# SCH_espweather_2025-04-03.net
KiCad netlist of a schematic drawn in EasyEDA
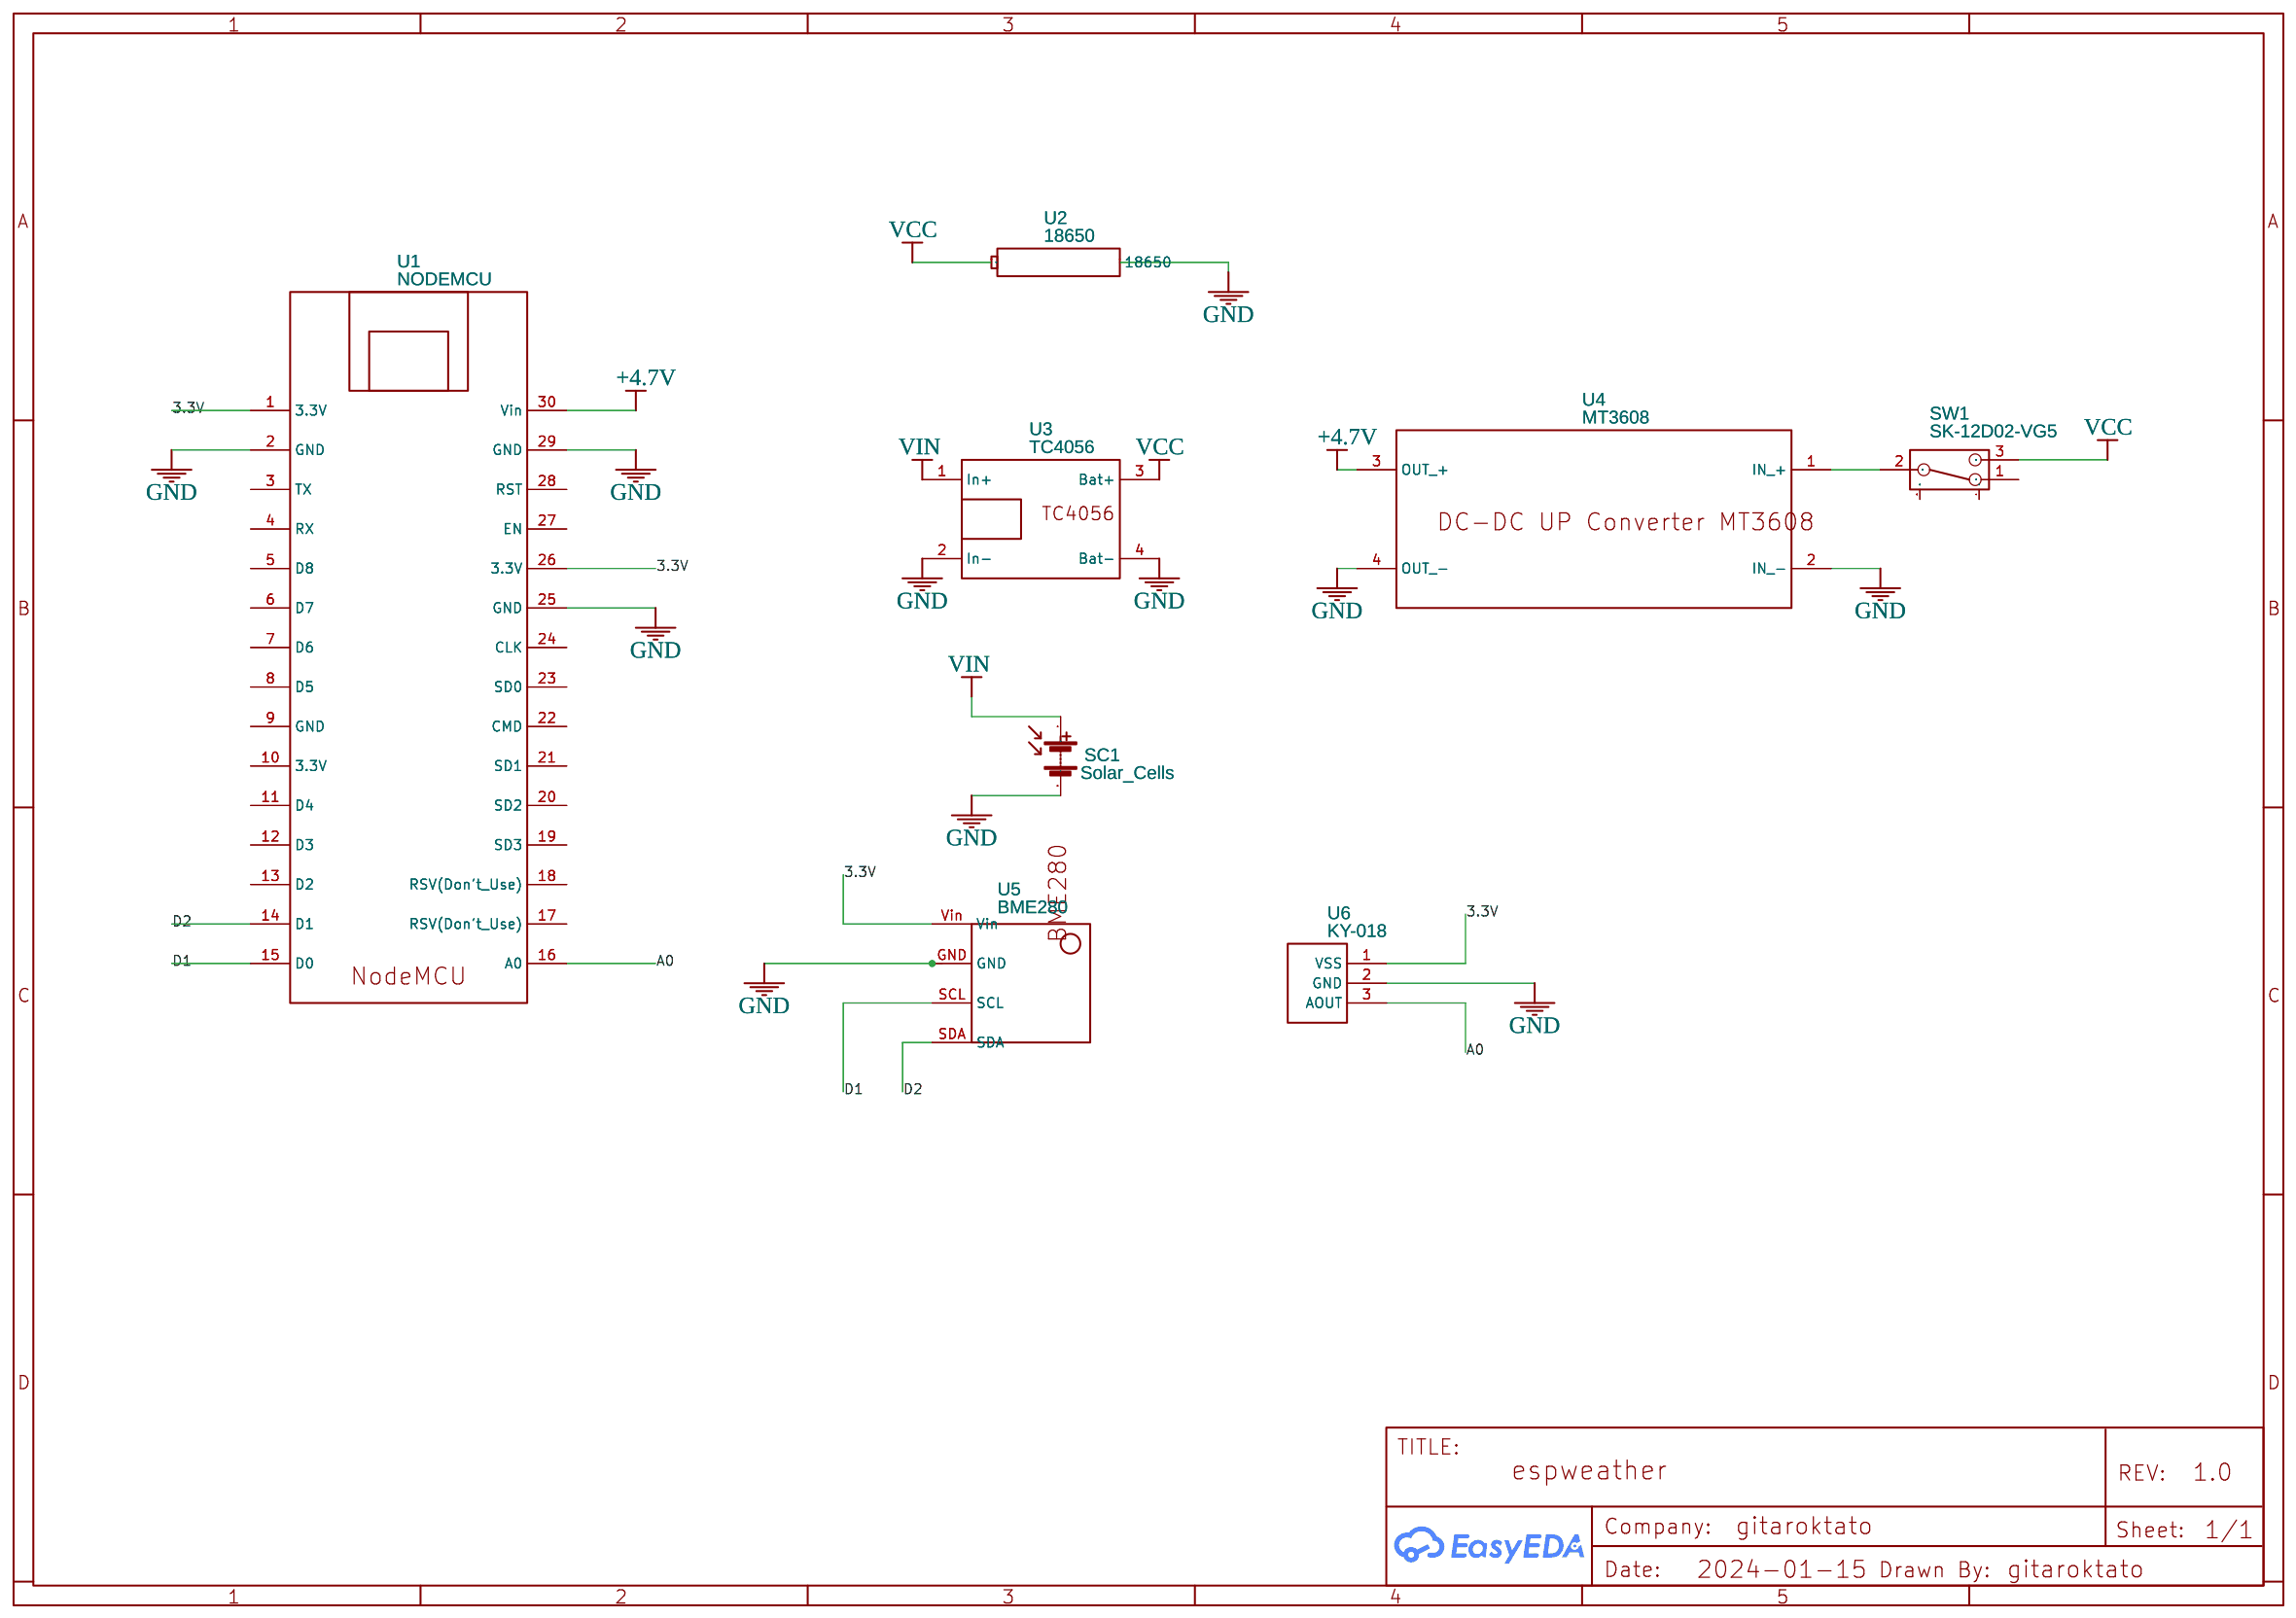
[diagram p0: schematic sheet]

(export (version "E")
  (design (tool "Eeschema 10.0.6"))
  (components
    (comp (ref "SC1") (value "Solar_Cells") (libsource (lib "") (part "Solar_Cells")))
    (comp (ref "SW1")
      (value "SK-12D02-VG5")
      (fields (field (name "Manufacturer") "Rectangular Connectors - Contacts"))
      (libsource (lib "") (part "SK-12D02-VG5"))
    )
    (comp (ref "U1") (value "NODEMCU") (libsource (lib "") (part "NODEMCU")))
    (comp (ref "U2") (value "18650") (libsource (lib "") (part "18650_2")))
    (comp (ref "U3")
      (value "TC4056")
      (fields (field (name "Manufacturer Part") "Lipo Charger FC-75"))
      (libsource (lib "") (part "LIPO CHARGER FC-75 PCCN"))
    )
    (comp (ref "U4") (value "MT3608") (libsource (lib "") (part "MT3608")))
    (comp (ref "U5") (value "BME280") (libsource (lib "") (part "BME280 COPY")))
    (comp (ref "U6")
      (value "KY-018")
      (fields (field (name "Manufacturer Part") "KY-018 Arduino Module"))
      (libsource (lib "") (part "KY-018 Arduino Module"))
    )
  )
  (nets
    (net (code "1") (name "+4.7V") (class "Default")
      (node (ref "U1") (pin "30") (pinfunction "Vin_30") (pintype "unspecified"))
      (node (ref "U4") (pin "3") (pinfunction "OUT_+_3") (pintype "unspecified"))
    )
    (net (code "2") (name "/3.3V") (class "Default")
      (node (ref "U1") (pin "1") (pinfunction "3.3V_1") (pintype "unspecified"))
      (node (ref "U1") (pin "26") (pinfunction "3.3V_26") (pintype "unspecified"))
      (node (ref "U5") (pin "Vin") (pinfunction "Vin_Vin") (pintype "unspecified"))
      (node (ref "U6") (pin "1") (pinfunction "VSS_1") (pintype "unspecified"))
    )
    (net (code "3") (name "/A0") (class "Default")
      (node (ref "U1") (pin "16") (pinfunction "A0_16") (pintype "unspecified"))
      (node (ref "U6") (pin "3") (pinfunction "AOUT_3") (pintype "unspecified"))
    )
    (net (code "4") (name "/D1") (class "Default")
      (node (ref "U1") (pin "15") (pinfunction "D0_15") (pintype "unspecified"))
      (node (ref "U5") (pin "SCL") (pinfunction "SCL_SCL") (pintype "unspecified"))
    )
    (net (code "5") (name "/D2") (class "Default")
      (node (ref "U1") (pin "14") (pinfunction "D1_14") (pintype "unspecified"))
      (node (ref "U5") (pin "SDA") (pinfunction "SDA_SDA") (pintype "unspecified"))
    )
    (net (code "6") (name "GND") (class "Default")
      (node (ref "SC1") (pin "2") (pinfunction "-_2") (pintype "unspecified"))
      (node (ref "U1") (pin "2") (pinfunction "GND_2") (pintype "unspecified"))
      (node (ref "U1") (pin "25") (pinfunction "GND_25") (pintype "unspecified"))
      (node (ref "U1") (pin "29") (pinfunction "GND_29") (pintype "unspecified"))
      (node (ref "U2") (pin "1") (pinfunction "18650_1") (pintype "unspecified"))
      (node (ref "U3") (pin "2") (pinfunction "In-_2") (pintype "unspecified"))
      (node (ref "U3") (pin "4") (pinfunction "Bat-_4") (pintype "unspecified"))
      (node (ref "U4") (pin "2") (pinfunction "IN_-_2") (pintype "unspecified"))
      (node (ref "U4") (pin "4") (pinfunction "OUT_-_4") (pintype "unspecified"))
      (node (ref "U5") (pin "GND") (pinfunction "GND_GND") (pintype "unspecified"))
      (node (ref "U6") (pin "2") (pinfunction "GND_2") (pintype "unspecified"))
    )
    (net (code "7") (name "Net-(U4-IN_+)") (class "Default")
      (node (ref "SW1") (pin "2") (pinfunction "2_2") (pintype "unspecified"))
      (node (ref "U4") (pin "1") (pinfunction "IN_+_1") (pintype "unspecified"))
    )
    (net (code "8") (name "VCC") (class "Default")
      (node (ref "SW1") (pin "3") (pinfunction "3_3") (pintype "unspecified"))
      (node (ref "U2") (pin "2") (pinfunction "2_2") (pintype "unspecified"))
      (node (ref "U3") (pin "3") (pinfunction "Bat+_3") (pintype "unspecified"))
    )
    (net (code "9") (name "VIN") (class "Default")
      (node (ref "SC1") (pin "1") (pinfunction "+_1") (pintype "unspecified"))
      (node (ref "U3") (pin "1") (pinfunction "In+_1") (pintype "unspecified"))
    )
    (net (code "10") (name "unconnected-(SW1-Pad1)") (class "Default")
      (node (ref "SW1") (pin "1") (pinfunction "1_1") (pintype "unspecified"))
    )
    (net (code "11") (name "unconnected-(SW1-Pad4)") (class "Default")
      (node (ref "SW1") (pin "4") (pinfunction "4_4") (pintype "unspecified"))
    )
    (net (code "12") (name "unconnected-(SW1-Pad5)") (class "Default")
      (node (ref "SW1") (pin "5") (pinfunction "5_5") (pintype "unspecified"))
    )
    (net (code "13") (name "unconnected-(U1-3.3V-Pad10)") (class "Default")
      (node (ref "U1") (pin "10") (pinfunction "3.3V_10") (pintype "unspecified"))
    )
    (net (code "14") (name "unconnected-(U1-CLK-Pad24)") (class "Default")
      (node (ref "U1") (pin "24") (pinfunction "CLK_24") (pintype "unspecified"))
    )
    (net (code "15") (name "unconnected-(U1-CMD-Pad22)") (class "Default")
      (node (ref "U1") (pin "22") (pinfunction "CMD_22") (pintype "unspecified"))
    )
    (net (code "16") (name "unconnected-(U1-D2-Pad13)") (class "Default")
      (node (ref "U1") (pin "13") (pinfunction "D2_13") (pintype "unspecified"))
    )
    (net (code "17") (name "unconnected-(U1-D3-Pad12)") (class "Default")
      (node (ref "U1") (pin "12") (pinfunction "D3_12") (pintype "unspecified"))
    )
    (net (code "18") (name "unconnected-(U1-D4-Pad11)") (class "Default")
      (node (ref "U1") (pin "11") (pinfunction "D4_11") (pintype "unspecified"))
    )
    (net (code "19") (name "unconnected-(U1-D5-Pad8)") (class "Default")
      (node (ref "U1") (pin "8") (pinfunction "D5_8") (pintype "unspecified"))
    )
    (net (code "20") (name "unconnected-(U1-D6-Pad7)") (class "Default")
      (node (ref "U1") (pin "7") (pinfunction "D6_7") (pintype "unspecified"))
    )
    (net (code "21") (name "unconnected-(U1-D7-Pad6)") (class "Default")
      (node (ref "U1") (pin "6") (pinfunction "D7_6") (pintype "unspecified"))
    )
    (net (code "22") (name "unconnected-(U1-D8-Pad5)") (class "Default")
      (node (ref "U1") (pin "5") (pinfunction "D8_5") (pintype "unspecified"))
    )
    (net (code "23") (name "unconnected-(U1-EN-Pad27)") (class "Default")
      (node (ref "U1") (pin "27") (pinfunction "EN_27") (pintype "unspecified"))
    )
    (net (code "24") (name "unconnected-(U1-GND-Pad9)") (class "Default")
      (node (ref "U1") (pin "9") (pinfunction "GND_9") (pintype "unspecified"))
    )
    (net (code "25") (name "unconnected-(U1-RST-Pad28)") (class "Default")
      (node (ref "U1") (pin "28") (pinfunction "RST_28") (pintype "unspecified"))
    )
    (net (code "26") (name "unconnected-(U1-RSV(Don't_Use)-Pad17)") (class "Default")
      (node (ref "U1") (pin "17") (pinfunction "RSV(Don't_Use)_17") (pintype "unspecified"))
    )
    (net (code "27") (name "unconnected-(U1-RSV(Don't_Use)-Pad18)") (class "Default")
      (node (ref "U1") (pin "18") (pinfunction "RSV(Don't_Use)_18") (pintype "unspecified"))
    )
    (net (code "28") (name "unconnected-(U1-RX-Pad4)") (class "Default")
      (node (ref "U1") (pin "4") (pinfunction "RX_4") (pintype "unspecified"))
    )
    (net (code "29") (name "unconnected-(U1-SD0-Pad23)") (class "Default")
      (node (ref "U1") (pin "23") (pinfunction "SD0_23") (pintype "unspecified"))
    )
    (net (code "30") (name "unconnected-(U1-SD1-Pad21)") (class "Default")
      (node (ref "U1") (pin "21") (pinfunction "SD1_21") (pintype "unspecified"))
    )
    (net (code "31") (name "unconnected-(U1-SD2-Pad20)") (class "Default")
      (node (ref "U1") (pin "20") (pinfunction "SD2_20") (pintype "unspecified"))
    )
    (net (code "32") (name "unconnected-(U1-SD3-Pad19)") (class "Default")
      (node (ref "U1") (pin "19") (pinfunction "SD3_19") (pintype "unspecified"))
    )
    (net (code "33") (name "unconnected-(U1-TX-Pad3)") (class "Default")
      (node (ref "U1") (pin "3") (pinfunction "TX_3") (pintype "unspecified"))
    )
  )
)
